# MLX75305_EvalBoard.net
KiCad netlist of a schematic drawn in Altium Designer
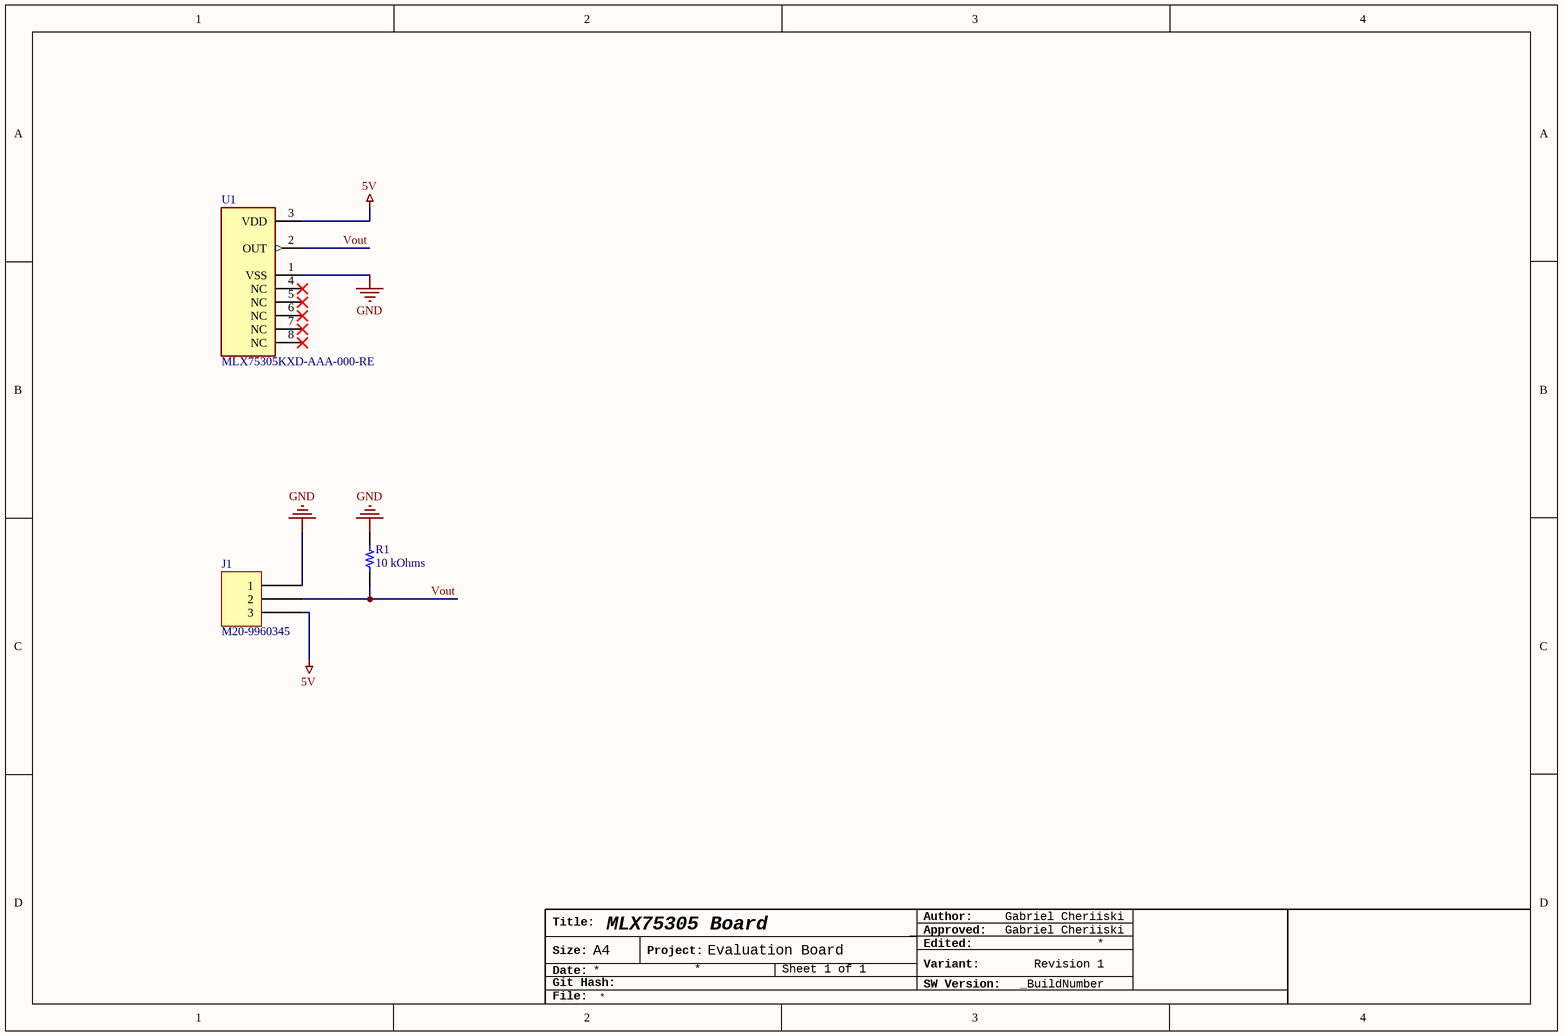
[diagram p0: MLX75305_EvalBoard.SchDoc]

(export (version "E")
  (design (tool "Eeschema 10.0.6"))
  (components
    (comp (ref "J1")
      (value "M20-9960345")
      (footprint "HARWIN M20-9960345")
      (description "CONN HEADER R/A 3POS 2.54MM")
      (fields (field (name "MANUFACTURER") "Harwin Inc."))
      (libsource (lib "Connectors - Rectangular Headers Male Pins") (part "M20-9960345"))
    )
    (comp (ref "R1")
      (value "10 kOhms")
      (footprint "RES 0805_2012")
      (description "RES SMD 10K OHM 5% 1/8W 0805")
      (fields (field (name "PART NUMBER") "AC0805JR-0710KL") (field (name "MANUFACTURER") "Yageo"))
      (libsource (lib "Resistors - Surface Mount - 0805") (part "AC0805JR-0710KL"))
    )
    (comp (ref "U1")
      (value "MLX75305KXD-AAA-000-RE")
      (footprint "SOIC127P599X175-8N")
      (description "Optical Sensor Ambient 850nm Voltage 8-SOIC (0.154, 3.90mm Width)")
      (fields (field (name "MF") "Melexis Technologies NV"))
      (libsource (lib "MLX75305KXD-AAA-000-RE") (part "MLX75305KXD-AAA-000-RE"))
    )
  )
  (nets
    (net (code "1") (name "/Vout") (class "Default")
      (node (ref "J1") (pin "2") (pinfunction "2_2") (pintype "passive"))
      (node (ref "R1") (pin "1") (pinfunction "1_1") (pintype "passive"))
      (node (ref "U1") (pin "2") (pinfunction "OUT_2") (pintype "output"))
    )
    (net (code "2") (name "5V") (class "Default")
      (node (ref "J1") (pin "3") (pinfunction "3_3") (pintype "passive"))
      (node (ref "U1") (pin "3") (pinfunction "VDD_3") (pintype "power_in"))
    )
    (net (code "3") (name "GND") (class "Default")
      (node (ref "J1") (pin "1") (pinfunction "1_1") (pintype "passive"))
      (node (ref "R1") (pin "2") (pinfunction "2_2") (pintype "passive"))
      (node (ref "U1") (pin "1") (pinfunction "VSS_1") (pintype "power_in"))
    )
    (net (code "4") (name "unconnected-(U1-NC-Pad4)") (class "Default")
      (node (ref "U1") (pin "4") (pinfunction "NC_4") (pintype "passive+no_connect"))
    )
    (net (code "5") (name "unconnected-(U1-NC-Pad5)") (class "Default")
      (node (ref "U1") (pin "5") (pinfunction "NC_5") (pintype "passive+no_connect"))
    )
    (net (code "6") (name "unconnected-(U1-NC-Pad6)") (class "Default")
      (node (ref "U1") (pin "6") (pinfunction "NC_6") (pintype "passive+no_connect"))
    )
    (net (code "7") (name "unconnected-(U1-NC-Pad7)") (class "Default")
      (node (ref "U1") (pin "7") (pinfunction "NC_7") (pintype "passive+no_connect"))
    )
    (net (code "8") (name "unconnected-(U1-NC-Pad8)") (class "Default")
      (node (ref "U1") (pin "8") (pinfunction "NC_8") (pintype "passive+no_connect"))
    )
  )
)
